# smduino.net
KiCad netlist of a schematic drawn in EAGLE
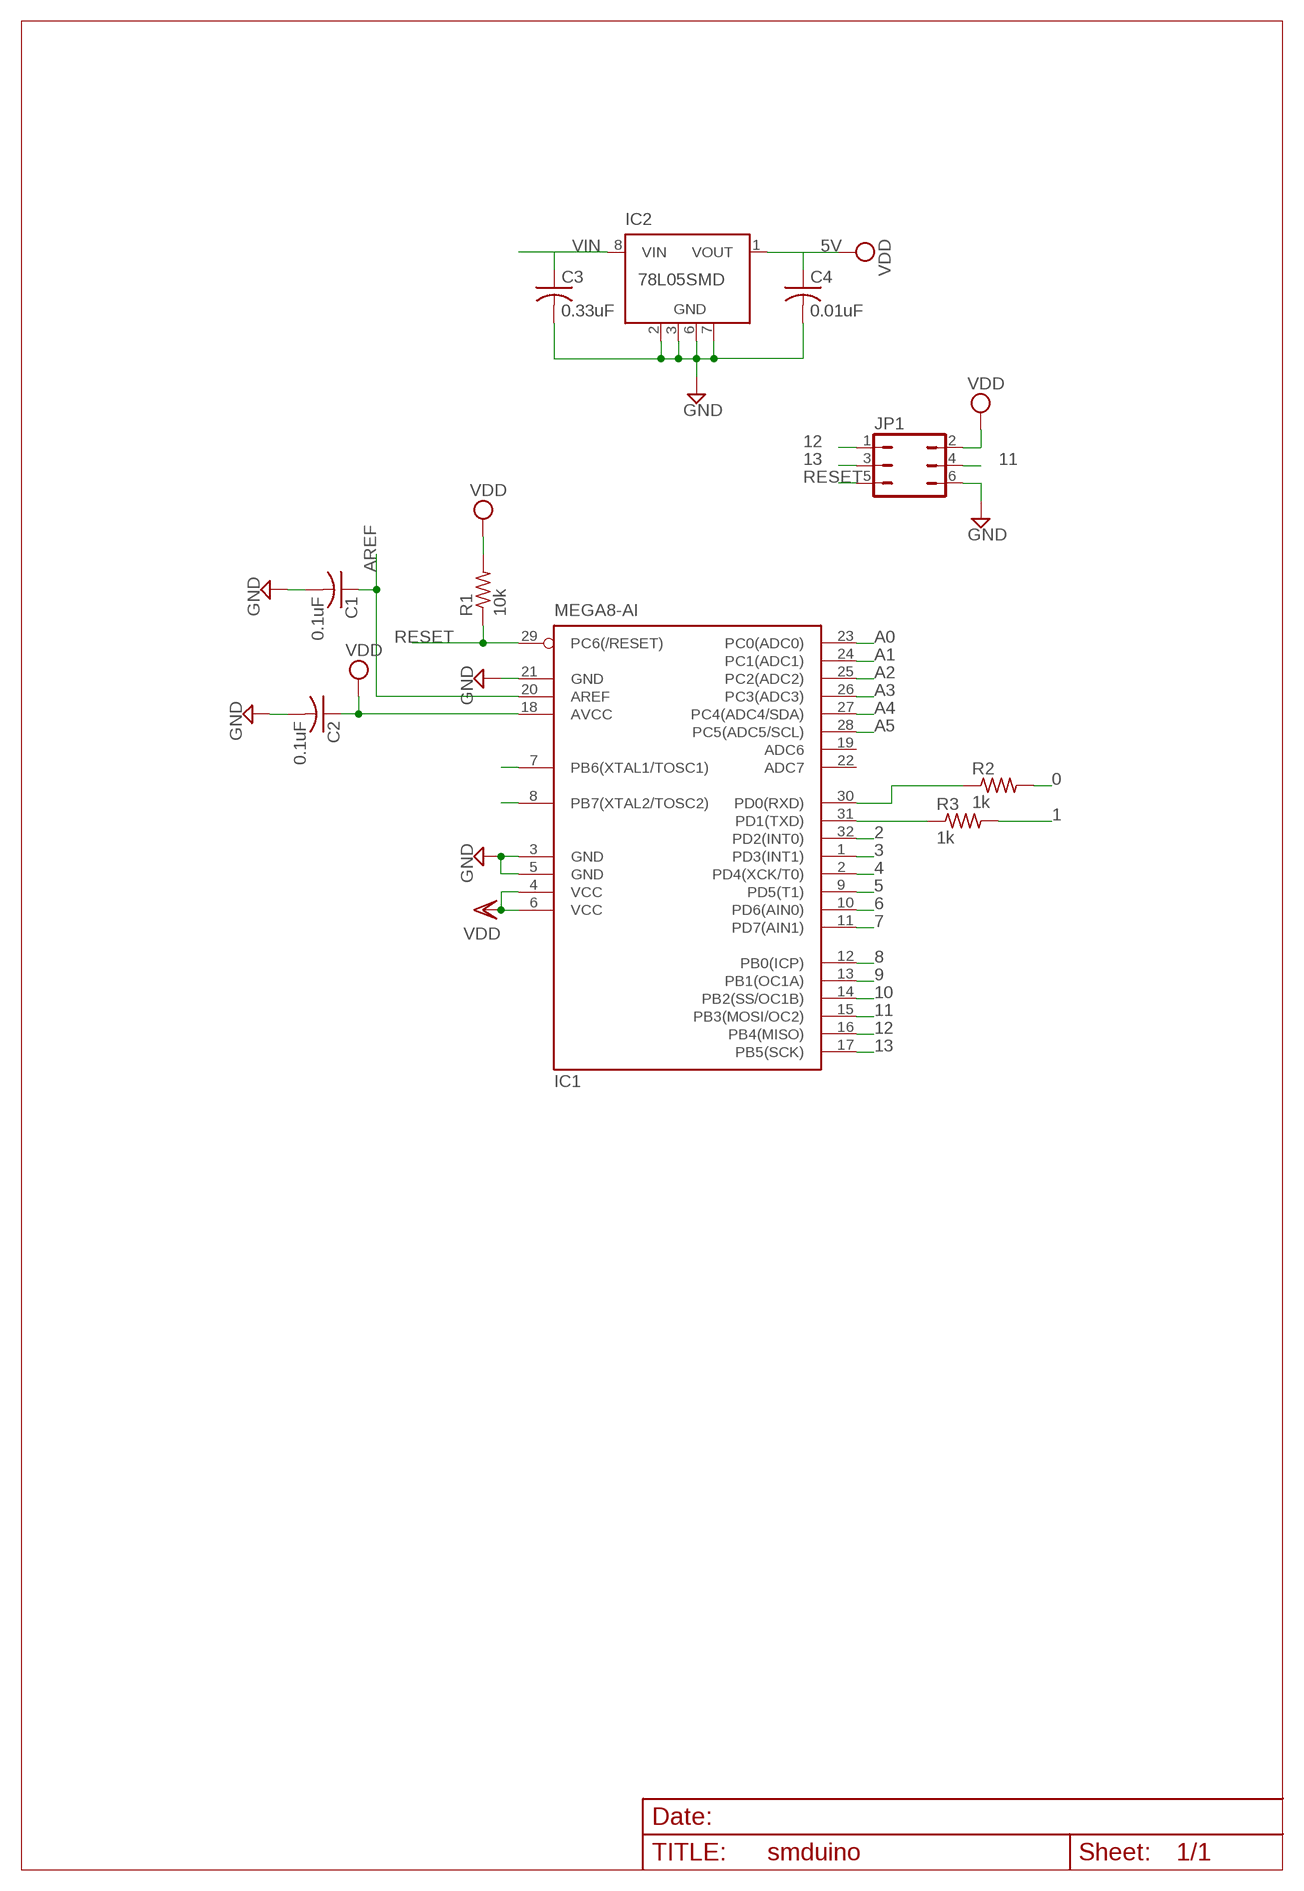
[diagram p0: schematic, sheet 1]

(export (version "E")
  (design (tool "Eeschema 10.0.6"))
  (components
    (comp (ref "C1")
      (value "0.1uF")
      (footprint "eagle-import:C0603")
      (libsource (lib "eagle-import") (part "C-USC0603"))
    )
    (comp (ref "C2")
      (value "0.1uF")
      (footprint "eagle-import:C0603")
      (libsource (lib "eagle-import") (part "C-USC0603"))
    )
    (comp (ref "C3")
      (value "0.33uF")
      (footprint "eagle-import:C0603")
      (libsource (lib "eagle-import") (part "C-USC0603"))
    )
    (comp (ref "C4")
      (value "0.01uF")
      (footprint "eagle-import:C0603")
      (libsource (lib "eagle-import") (part "C-USC0603"))
    )
    (comp (ref "IC1")
      (value "MEGA8-AI")
      (footprint "eagle-import:TQFP32-08")
      (fields (field (name "MPN") "ATMEGA8-16AU"))
      (libsource (lib "eagle-import") (part "MEGA8-AI"))
    )
    (comp (ref "IC2")
      (value "78L05SMD")
      (footprint "eagle-import:SO08")
      (libsource (lib "eagle-import") (part "78LSMD05"))
    )
    (comp (ref "JP1")
      (value "JP3Q")
      (footprint "eagle-import:JP3Q")
      (libsource (lib "eagle-import") (part "JP3Q"))
    )
    (comp (ref "R1")
      (value "10k")
      (footprint "eagle-import:R0603")
      (libsource (lib "eagle-import") (part "R-US_R0603"))
    )
    (comp (ref "R2")
      (value "1k")
      (footprint "eagle-import:R0603")
      (libsource (lib "eagle-import") (part "R-US_R0603"))
    )
    (comp (ref "R3")
      (value "1k")
      (footprint "eagle-import:R0603")
      (libsource (lib "eagle-import") (part "R-US_R0603"))
    )
  )
  (nets
    (net (code "1") (name "/0") (class "Default")
      (node (ref "R2") (pin "2") (pinfunction "2_2") (pintype "passive"))
    )
    (net (code "2") (name "/1") (class "Default")
      (node (ref "R3") (pin "2") (pinfunction "2_2") (pintype "passive"))
    )
    (net (code "3") (name "/2") (class "Default")
      (node (ref "IC1") (pin "32") (pinfunction "PD2(INT0)_32") (pintype "bidirectional"))
    )
    (net (code "4") (name "/3") (class "Default")
      (node (ref "IC1") (pin "1") (pinfunction "PD3(INT1)_1") (pintype "bidirectional"))
    )
    (net (code "5") (name "/4") (class "Default")
      (node (ref "IC1") (pin "2") (pinfunction "PD4(XCK/T0)_2") (pintype "bidirectional"))
    )
    (net (code "6") (name "/5") (class "Default")
      (node (ref "IC1") (pin "9") (pinfunction "PD5(T1)_9") (pintype "bidirectional"))
    )
    (net (code "7") (name "/6") (class "Default")
      (node (ref "IC1") (pin "10") (pinfunction "PD6(AIN0)_10") (pintype "bidirectional"))
    )
    (net (code "8") (name "/7") (class "Default")
      (node (ref "IC1") (pin "11") (pinfunction "PD7(AIN1)_11") (pintype "bidirectional"))
    )
    (net (code "9") (name "/8") (class "Default")
      (node (ref "IC1") (pin "12") (pinfunction "PB0(ICP)_12") (pintype "bidirectional"))
    )
    (net (code "10") (name "/9") (class "Default")
      (node (ref "IC1") (pin "13") (pinfunction "PB1(OC1A)_13") (pintype "bidirectional"))
    )
    (net (code "11") (name "/10") (class "Default")
      (node (ref "IC1") (pin "14") (pinfunction "PB2(SS/OC1B)_14") (pintype "bidirectional"))
    )
    (net (code "12") (name "/11") (class "Default")
      (node (ref "IC1") (pin "15") (pinfunction "PB3(MOSI/OC2)_15") (pintype "bidirectional"))
      (node (ref "JP1") (pin "4") (pinfunction "4_4") (pintype "passive"))
    )
    (net (code "13") (name "/12") (class "Default")
      (node (ref "IC1") (pin "16") (pinfunction "PB4(MISO)_16") (pintype "bidirectional"))
      (node (ref "JP1") (pin "1") (pinfunction "1_1") (pintype "passive"))
    )
    (net (code "14") (name "/13") (class "Default")
      (node (ref "IC1") (pin "17") (pinfunction "PB5(SCK)_17") (pintype "bidirectional"))
      (node (ref "JP1") (pin "3") (pinfunction "3_3") (pintype "passive"))
    )
    (net (code "15") (name "/A0") (class "Default")
      (node (ref "IC1") (pin "23") (pinfunction "PC0(ADC0)_23") (pintype "bidirectional"))
    )
    (net (code "16") (name "/A1") (class "Default")
      (node (ref "IC1") (pin "24") (pinfunction "PC1(ADC1)_24") (pintype "bidirectional"))
    )
    (net (code "17") (name "/A2") (class "Default")
      (node (ref "IC1") (pin "25") (pinfunction "PC2(ADC2)_25") (pintype "bidirectional"))
    )
    (net (code "18") (name "/A3") (class "Default")
      (node (ref "IC1") (pin "26") (pinfunction "PC3(ADC3)_26") (pintype "bidirectional"))
    )
    (net (code "19") (name "/A4") (class "Default")
      (node (ref "IC1") (pin "27") (pinfunction "PC4(ADC4/SDA)_27") (pintype "bidirectional"))
    )
    (net (code "20") (name "/A5") (class "Default")
      (node (ref "IC1") (pin "28") (pinfunction "PC5(ADC5/SCL)_28") (pintype "bidirectional"))
    )
    (net (code "21") (name "/AREF") (class "Default")
      (node (ref "C1") (pin "1") (pinfunction "1_1") (pintype "passive"))
      (node (ref "IC1") (pin "20") (pinfunction "AREF_20") (pintype "passive"))
    )
    (net (code "22") (name "/RESET") (class "Default")
      (node (ref "IC1") (pin "29") (pinfunction "PC6(/RESET)_29") (pintype "bidirectional"))
      (node (ref "JP1") (pin "5") (pinfunction "5_5") (pintype "passive"))
      (node (ref "R1") (pin "1") (pinfunction "1_1") (pintype "passive"))
    )
    (net (code "23") (name "/VIN") (class "Default")
      (node (ref "C3") (pin "1") (pinfunction "1_1") (pintype "passive"))
      (node (ref "IC2") (pin "8") (pinfunction "VIN_8") (pintype "passive"))
    )
    (net (code "24") (name "GND") (class "Default")
      (node (ref "C1") (pin "2") (pinfunction "2_2") (pintype "passive"))
      (node (ref "C2") (pin "2") (pinfunction "2_2") (pintype "passive"))
      (node (ref "C3") (pin "2") (pinfunction "2_2") (pintype "passive"))
      (node (ref "C4") (pin "2") (pinfunction "2_2") (pintype "passive"))
      (node (ref "IC1") (pin "21") (pinfunction "GND_21") (pintype "power_in"))
      (node (ref "IC1") (pin "3") (pinfunction "GND_3") (pintype "power_in"))
      (node (ref "IC1") (pin "5") (pinfunction "GND_5") (pintype "power_in"))
      (node (ref "IC2") (pin "2") (pinfunction "GND_2") (pintype "power_in"))
      (node (ref "IC2") (pin "3") (pinfunction "GND_3") (pintype "power_in"))
      (node (ref "IC2") (pin "6") (pinfunction "GND_6") (pintype "power_in"))
      (node (ref "IC2") (pin "7") (pinfunction "GND_7") (pintype "power_in"))
      (node (ref "JP1") (pin "6") (pinfunction "6_6") (pintype "passive"))
    )
    (net (code "25") (name "Net-(IC1-PD0(RXD))") (class "Default")
      (node (ref "IC1") (pin "30") (pinfunction "PD0(RXD)_30") (pintype "bidirectional"))
      (node (ref "R2") (pin "1") (pinfunction "1_1") (pintype "passive"))
    )
    (net (code "26") (name "Net-(IC1-PD1(TXD))") (class "Default")
      (node (ref "IC1") (pin "31") (pinfunction "PD1(TXD)_31") (pintype "bidirectional"))
      (node (ref "R3") (pin "1") (pinfunction "1_1") (pintype "passive"))
    )
    (net (code "27") (name "VDD") (class "Default")
      (node (ref "C2") (pin "1") (pinfunction "1_1") (pintype "passive"))
      (node (ref "C4") (pin "1") (pinfunction "1_1") (pintype "passive"))
      (node (ref "IC1") (pin "18") (pinfunction "AVCC_18") (pintype "power_in"))
      (node (ref "IC1") (pin "4") (pinfunction "VCC_4") (pintype "power_in"))
      (node (ref "IC1") (pin "6") (pinfunction "VCC_6") (pintype "power_in"))
      (node (ref "IC2") (pin "1") (pinfunction "VOUT_1") (pintype "output"))
      (node (ref "JP1") (pin "2") (pinfunction "2_2") (pintype "passive"))
      (node (ref "R1") (pin "2") (pinfunction "2_2") (pintype "passive"))
    )
    (net (code "28") (name "unconnected-(IC1-ADC6-Pad19)") (class "Default")
      (node (ref "IC1") (pin "19") (pinfunction "ADC6_19") (pintype "bidirectional"))
    )
    (net (code "29") (name "unconnected-(IC1-ADC7-Pad22)") (class "Default")
      (node (ref "IC1") (pin "22") (pinfunction "ADC7_22") (pintype "bidirectional"))
    )
    (net (code "30") (name "unconnected-(IC1-PB6(XTAL1{slash}TOSC1)-Pad7)") (class "Default")
      (node (ref "IC1") (pin "7") (pinfunction "PB6(XTAL1/TOSC1)_7") (pintype "bidirectional"))
    )
    (net (code "31") (name "unconnected-(IC1-PB7(XTAL2{slash}TOSC2)-Pad8)") (class "Default")
      (node (ref "IC1") (pin "8") (pinfunction "PB7(XTAL2/TOSC2)_8") (pintype "bidirectional"))
    )
  )
)
